# Controller.net
KiCad netlist of a schematic drawn in EAGLE
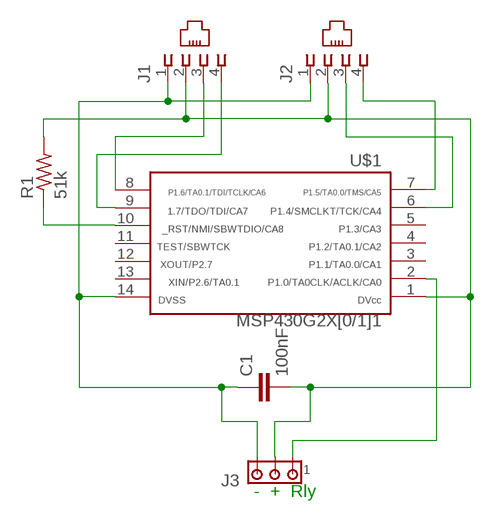
[diagram p0: schematic, sheet 1]

(export (version "E")
  (design (tool "Eeschema 10.0.6"))
  (components
    (comp (ref "C1")
      (value "100nF")
      (footprint "eagle-import:C2.5-2")
      (libsource (lib "eagle-import") (part "C2.5/2"))
    )
    (comp (ref "J1")
      (value "555166-3")
      (footprint "eagle-import:555166-3")
      (libsource (lib "eagle-import") (part "555166-3"))
    )
    (comp (ref "J2")
      (value "555166-3")
      (footprint "eagle-import:555166-3")
      (libsource (lib "eagle-import") (part "555166-3"))
    )
    (comp (ref "J3")
      (value "MTA03-100")
      (footprint "eagle-import:10X03MTA")
      (libsource (lib "eagle-import") (part "MTA03-100"))
    )
    (comp (ref "R1")
      (value "51k")
      (footprint "eagle-import:R0603")
      (libsource (lib "eagle-import") (part "R-US_R0603"))
    )
    (comp (ref "U$1")
      (value "G2X[0/1]1---N14")
      (footprint "eagle-import:N14")
      (libsource (lib "eagle-import") (part "G2X[0/1]1---N14"))
    )
  )
  (nets
    (net (code "1") (name "Net-(C1-Pad1)") (class "Default")
      (node (ref "C1") (pin "1") (pinfunction "1_1") (pintype "passive"))
      (node (ref "J1") (pin "1") (pinfunction "1_1") (pintype "passive"))
      (node (ref "J2") (pin "1") (pinfunction "1_1") (pintype "passive"))
      (node (ref "J3") (pin "3") (pinfunction "3_3") (pintype "passive"))
      (node (ref "U$1") (pin "14") (pinfunction "14_14") (pintype "bidirectional"))
    )
    (net (code "2") (name "Net-(C1-Pad2)") (class "Default")
      (node (ref "C1") (pin "2") (pinfunction "2_2") (pintype "passive"))
      (node (ref "J1") (pin "2") (pinfunction "2_2") (pintype "passive"))
      (node (ref "J2") (pin "2") (pinfunction "2_2") (pintype "passive"))
      (node (ref "J3") (pin "2") (pinfunction "2_2") (pintype "passive"))
      (node (ref "R1") (pin "2") (pinfunction "2_2") (pintype "passive"))
      (node (ref "U$1") (pin "1") (pinfunction "1_1") (pintype "bidirectional"))
    )
    (net (code "3") (name "Net-(J1-Pad3)") (class "Default")
      (node (ref "J1") (pin "3") (pinfunction "3_3") (pintype "passive"))
      (node (ref "U$1") (pin "8") (pinfunction "8_8") (pintype "bidirectional"))
    )
    (net (code "4") (name "Net-(J1-Pad4)") (class "Default")
      (node (ref "J1") (pin "4") (pinfunction "4_4") (pintype "passive"))
      (node (ref "U$1") (pin "9") (pinfunction "9_9") (pintype "bidirectional"))
    )
    (net (code "5") (name "Net-(J2-Pad3)") (class "Default")
      (node (ref "J2") (pin "3") (pinfunction "3_3") (pintype "passive"))
      (node (ref "U$1") (pin "6") (pinfunction "6_6") (pintype "bidirectional"))
    )
    (net (code "6") (name "Net-(J2-Pad4)") (class "Default")
      (node (ref "J2") (pin "4") (pinfunction "4_4") (pintype "passive"))
      (node (ref "U$1") (pin "7") (pinfunction "7_7") (pintype "bidirectional"))
    )
    (net (code "7") (name "Net-(J3-Pad1)") (class "Default")
      (node (ref "J3") (pin "1") (pinfunction "1_1") (pintype "passive"))
      (node (ref "U$1") (pin "2") (pinfunction "2_2") (pintype "bidirectional"))
    )
    (net (code "8") (name "Net-(R1-Pad1)") (class "Default")
      (node (ref "R1") (pin "1") (pinfunction "1_1") (pintype "passive"))
      (node (ref "U$1") (pin "10") (pinfunction "10_10") (pintype "bidirectional"))
    )
    (net (code "9") (name "unconnected-(U$1-Pad3)") (class "Default")
      (node (ref "U$1") (pin "3") (pinfunction "3_3") (pintype "bidirectional"))
    )
    (net (code "10") (name "unconnected-(U$1-Pad4)") (class "Default")
      (node (ref "U$1") (pin "4") (pinfunction "4_4") (pintype "bidirectional"))
    )
    (net (code "11") (name "unconnected-(U$1-Pad5)") (class "Default")
      (node (ref "U$1") (pin "5") (pinfunction "5_5") (pintype "bidirectional"))
    )
    (net (code "12") (name "unconnected-(U$1-Pad11)") (class "Default")
      (node (ref "U$1") (pin "11") (pinfunction "11_11") (pintype "bidirectional"))
    )
    (net (code "13") (name "unconnected-(U$1-Pad12)") (class "Default")
      (node (ref "U$1") (pin "12") (pinfunction "12_12") (pintype "bidirectional"))
    )
    (net (code "14") (name "unconnected-(U$1-Pad13)") (class "Default")
      (node (ref "U$1") (pin "13") (pinfunction "13_13") (pintype "bidirectional"))
    )
  )
)
